# SD_A2.net
KiCad netlist of a schematic drawn in EAGLE
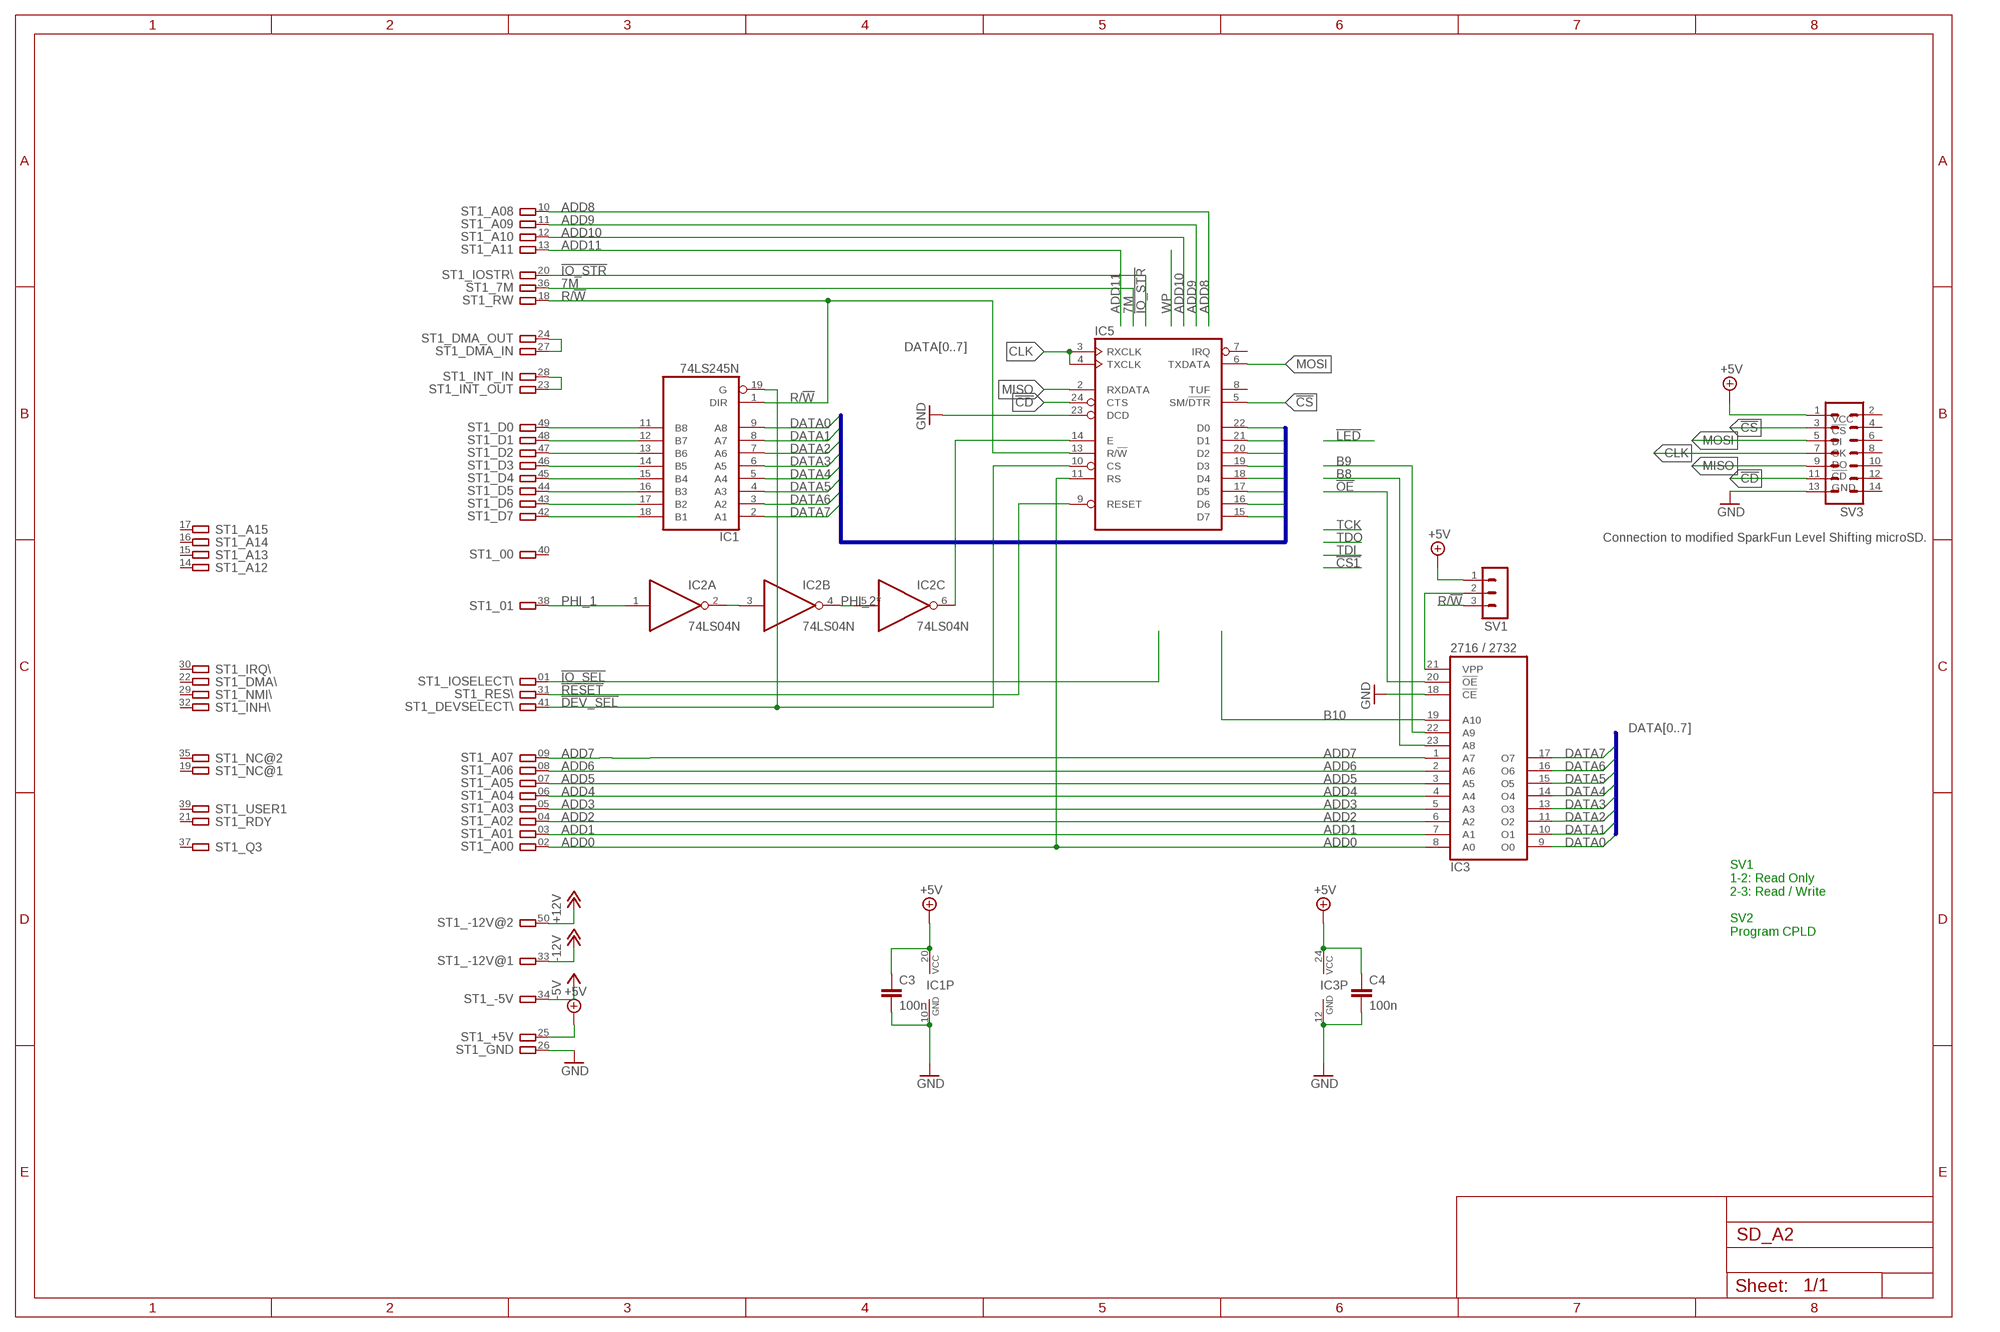
[diagram p0: schematic, sheet 1]

(export (version "E")
  (design (tool "Eeschema 10.0.6"))
  (components
    (comp (ref "C3")
      (value "100n")
      (footprint "eagle-import:C0603K")
      (libsource (lib "eagle-import") (part "C-EUC0603K"))
    )
    (comp (ref "C4")
      (value "100n")
      (footprint "eagle-import:C0603K")
      (libsource (lib "eagle-import") (part "C-EUC0603K"))
    )
    (comp (ref "IC1")
      (value "74LS245N")
      (footprint "eagle-import:DIL20")
      (libsource (lib "eagle-import") (part "74245NLS"))
    )
    (comp (ref "IC2")
      (value "74LS04N")
      (footprint "eagle-import:DIL14")
      (libsource (lib "eagle-import") (part "7404NLS"))
    )
    (comp (ref "IC3")
      (value "2716 / 2732")
      (footprint "eagle-import:DIL24")
      (libsource (lib "eagle-import") (part "2716"))
    )
    (comp (ref "IC5")
      (value "6852")
      (footprint "eagle-import:DIL24")
      (libsource (lib "eagle-import") (part "6852"))
    )
    (comp (ref "ST1")
      (value "A2-50PINSLOT1-3")
      (footprint "eagle-import:A2-50PIN-SL1-3")
      (libsource (lib "eagle-import") (part "A2-50PINSLOT1-3"))
    )
    (comp (ref "SV1")
      (value "MA03-1")
      (footprint "eagle-import:MA03-1")
      (libsource (lib "eagle-import") (part "MA03-1"))
    )
    (comp (ref "SV3")
      (value "MA07-2")
      (footprint "eagle-import:MA07-2")
      (libsource (lib "eagle-import") (part "MA07-2"))
    )
  )
  (nets
    (net (code "1") (name "+5V") (class "Default")
      (node (ref "C3") (pin "1") (pinfunction "1_1") (pintype "passive"))
      (node (ref "C4") (pin "1") (pinfunction "1_1") (pintype "passive"))
      (node (ref "IC1") (pin "20") (pinfunction "VCC_20") (pintype "power_in"))
      (node (ref "IC3") (pin "24") (pinfunction "VCC_24") (pintype "power_in"))
      (node (ref "ST1") (pin "25") (pinfunction "P_25") (pintype "bidirectional"))
      (node (ref "SV1") (pin "1") (pinfunction "1_1") (pintype "passive"))
      (node (ref "SV3") (pin "1") (pinfunction "1_1") (pintype "passive"))
    )
    (net (code "2") (name "+12V") (class "Default")
      (node (ref "ST1") (pin "50") (pinfunction "P_50") (pintype "bidirectional"))
    )
    (net (code "3") (name "-5V") (class "Default")
      (node (ref "ST1") (pin "34") (pinfunction "P_34") (pintype "bidirectional"))
    )
    (net (code "4") (name "-12V") (class "Default")
      (node (ref "ST1") (pin "33") (pinfunction "P_33") (pintype "bidirectional"))
    )
    (net (code "5") (name "/7M") (class "Default")
      (node (ref "ST1") (pin "36") (pinfunction "P_36") (pintype "bidirectional"))
    )
    (net (code "6") (name "/ADD0") (class "Default")
      (node (ref "IC3") (pin "8") (pinfunction "A0_8") (pintype "input"))
      (node (ref "IC5") (pin "11") (pinfunction "RS_11") (pintype "input"))
      (node (ref "ST1") (pin "02") (pinfunction "P_02") (pintype "bidirectional"))
    )
    (net (code "7") (name "/ADD1") (class "Default")
      (node (ref "IC3") (pin "7") (pinfunction "A1_7") (pintype "input"))
      (node (ref "ST1") (pin "03") (pinfunction "P_03") (pintype "bidirectional"))
    )
    (net (code "8") (name "/ADD2") (class "Default")
      (node (ref "IC3") (pin "6") (pinfunction "A2_6") (pintype "input"))
      (node (ref "ST1") (pin "04") (pinfunction "P_04") (pintype "bidirectional"))
    )
    (net (code "9") (name "/ADD3") (class "Default")
      (node (ref "IC3") (pin "5") (pinfunction "A3_5") (pintype "input"))
      (node (ref "ST1") (pin "05") (pinfunction "P_05") (pintype "bidirectional"))
    )
    (net (code "10") (name "/ADD4") (class "Default")
      (node (ref "IC3") (pin "4") (pinfunction "A4_4") (pintype "input"))
      (node (ref "ST1") (pin "06") (pinfunction "P_06") (pintype "bidirectional"))
    )
    (net (code "11") (name "/ADD5") (class "Default")
      (node (ref "IC3") (pin "3") (pinfunction "A5_3") (pintype "input"))
      (node (ref "ST1") (pin "07") (pinfunction "P_07") (pintype "bidirectional"))
    )
    (net (code "12") (name "/ADD6") (class "Default")
      (node (ref "IC3") (pin "2") (pinfunction "A6_2") (pintype "input"))
      (node (ref "ST1") (pin "08") (pinfunction "P_08") (pintype "bidirectional"))
    )
    (net (code "13") (name "/ADD7") (class "Default")
      (node (ref "IC3") (pin "1") (pinfunction "A7_1") (pintype "input"))
      (node (ref "ST1") (pin "09") (pinfunction "P_09") (pintype "bidirectional"))
    )
    (net (code "14") (name "/ADD8") (class "Default")
      (node (ref "ST1") (pin "10") (pinfunction "P_10") (pintype "bidirectional"))
    )
    (net (code "15") (name "/ADD9") (class "Default")
      (node (ref "ST1") (pin "11") (pinfunction "P_11") (pintype "bidirectional"))
    )
    (net (code "16") (name "/ADD10") (class "Default")
      (node (ref "ST1") (pin "12") (pinfunction "P_12") (pintype "bidirectional"))
    )
    (net (code "17") (name "/ADD11") (class "Default")
      (node (ref "ST1") (pin "13") (pinfunction "P_13") (pintype "bidirectional"))
    )
    (net (code "18") (name "/B8") (class "Default")
      (node (ref "IC3") (pin "23") (pinfunction "A8_23") (pintype "input"))
    )
    (net (code "19") (name "/B9") (class "Default")
      (node (ref "IC3") (pin "22") (pinfunction "A9_22") (pintype "input"))
    )
    (net (code "20") (name "/B10") (class "Default")
      (node (ref "IC3") (pin "19") (pinfunction "A10_19") (pintype "input"))
    )
    (net (code "21") (name "/DATA0") (class "Default")
      (node (ref "IC1") (pin "9") (pinfunction "A8_9") (pintype "bidirectional"))
      (node (ref "IC3") (pin "9") (pinfunction "O0_9") (pintype "tri_state"))
      (node (ref "IC5") (pin "22") (pinfunction "D0_22") (pintype "bidirectional"))
    )
    (net (code "22") (name "/DATA1") (class "Default")
      (node (ref "IC1") (pin "8") (pinfunction "A7_8") (pintype "bidirectional"))
      (node (ref "IC3") (pin "10") (pinfunction "O1_10") (pintype "tri_state"))
      (node (ref "IC5") (pin "21") (pinfunction "D1_21") (pintype "bidirectional"))
    )
    (net (code "23") (name "/DATA2") (class "Default")
      (node (ref "IC1") (pin "7") (pinfunction "A6_7") (pintype "bidirectional"))
      (node (ref "IC3") (pin "11") (pinfunction "O2_11") (pintype "tri_state"))
      (node (ref "IC5") (pin "20") (pinfunction "D2_20") (pintype "bidirectional"))
    )
    (net (code "24") (name "/DATA3") (class "Default")
      (node (ref "IC1") (pin "6") (pinfunction "A5_6") (pintype "bidirectional"))
      (node (ref "IC3") (pin "13") (pinfunction "O3_13") (pintype "tri_state"))
      (node (ref "IC5") (pin "19") (pinfunction "D3_19") (pintype "bidirectional"))
    )
    (net (code "25") (name "/DATA4") (class "Default")
      (node (ref "IC1") (pin "5") (pinfunction "A4_5") (pintype "bidirectional"))
      (node (ref "IC3") (pin "14") (pinfunction "O4_14") (pintype "tri_state"))
      (node (ref "IC5") (pin "18") (pinfunction "D4_18") (pintype "bidirectional"))
    )
    (net (code "26") (name "/DATA5") (class "Default")
      (node (ref "IC1") (pin "4") (pinfunction "A3_4") (pintype "bidirectional"))
      (node (ref "IC3") (pin "15") (pinfunction "O5_15") (pintype "tri_state"))
      (node (ref "IC5") (pin "17") (pinfunction "D5_17") (pintype "bidirectional"))
    )
    (net (code "27") (name "/DATA6") (class "Default")
      (node (ref "IC1") (pin "3") (pinfunction "A2_3") (pintype "bidirectional"))
      (node (ref "IC3") (pin "16") (pinfunction "O6_16") (pintype "tri_state"))
      (node (ref "IC5") (pin "16") (pinfunction "D6_16") (pintype "bidirectional"))
    )
    (net (code "28") (name "/DATA7") (class "Default")
      (node (ref "IC1") (pin "2") (pinfunction "A1_2") (pintype "bidirectional"))
      (node (ref "IC3") (pin "17") (pinfunction "O7_17") (pintype "tri_state"))
      (node (ref "IC5") (pin "15") (pinfunction "D7_15") (pintype "bidirectional"))
    )
    (net (code "30") (name "/PHI_1") (class "Default")
      (node (ref "IC2") (pin "1") (pinfunction "I_1") (pintype "input"))
      (node (ref "ST1") (pin "38") (pinfunction "P_38") (pintype "bidirectional"))
    )
    (net (code "31") (name "/PHI_2*") (class "Default")
      (node (ref "IC2") (pin "6") (pinfunction "O_6") (pintype "output"))
      (node (ref "IC5") (pin "14") (pinfunction "E_14") (pintype "input"))
    )
    (net (code "32") (name "/R{slash}~{W}") (class "Default")
      (node (ref "IC1") (pin "1") (pinfunction "DIR_1") (pintype "input"))
      (node (ref "IC5") (pin "13") (pinfunction "R/~{W}_13") (pintype "input"))
      (node (ref "ST1") (pin "18") (pinfunction "P_18") (pintype "bidirectional"))
      (node (ref "SV1") (pin "3") (pinfunction "3_3") (pintype "passive"))
    )
    (net (code "37") (name "/~{CD}") (class "Default")
      (node (ref "IC5") (pin "24") (pinfunction "CTS_24") (pintype "input"))
      (node (ref "SV3") (pin "11") (pinfunction "11_11") (pintype "passive"))
    )
    (net (code "39") (name "/~{CS}") (class "Default")
      (node (ref "IC5") (pin "5") (pinfunction "SM/~{DTR}_5") (pintype "output"))
      (node (ref "SV3") (pin "3") (pinfunction "3_3") (pintype "passive"))
    )
    (net (code "40") (name "/~{DEV_SEL}") (class "Default")
      (node (ref "IC1") (pin "19") (pinfunction "G_19") (pintype "input"))
      (node (ref "IC5") (pin "10") (pinfunction "CS_10") (pintype "input"))
      (node (ref "ST1") (pin "41") (pinfunction "P_41") (pintype "bidirectional"))
    )
    (net (code "41") (name "/~{IO_SEL}") (class "Default")
      (node (ref "ST1") (pin "01") (pinfunction "P_01") (pintype "bidirectional"))
    )
    (net (code "42") (name "/~{IO_STR}") (class "Default")
      (node (ref "ST1") (pin "20") (pinfunction "P_20") (pintype "bidirectional"))
    )
    (net (code "44") (name "/~{OE}") (class "Default")
      (node (ref "IC3") (pin "20") (pinfunction "~{OE}_20") (pintype "input"))
    )
    (net (code "45") (name "/~{RESET}") (class "Default")
      (node (ref "IC5") (pin "9") (pinfunction "RESET_9") (pintype "input"))
      (node (ref "ST1") (pin "31") (pinfunction "P_31") (pintype "bidirectional"))
    )
    (net (code "46") (name "CLK") (class "Default")
      (node (ref "IC5") (pin "3") (pinfunction "RXCLK_3") (pintype "input"))
      (node (ref "IC5") (pin "4") (pinfunction "TXCLK_4") (pintype "input"))
      (node (ref "SV3") (pin "7") (pinfunction "7_7") (pintype "passive"))
    )
    (net (code "47") (name "GND") (class "Default")
      (node (ref "C3") (pin "2") (pinfunction "2_2") (pintype "passive"))
      (node (ref "C4") (pin "2") (pinfunction "2_2") (pintype "passive"))
      (node (ref "IC1") (pin "10") (pinfunction "GND_10") (pintype "power_in"))
      (node (ref "IC3") (pin "12") (pinfunction "GND_12") (pintype "power_in"))
      (node (ref "IC3") (pin "18") (pinfunction "~{CE}_18") (pintype "input"))
      (node (ref "IC5") (pin "23") (pinfunction "DCD_23") (pintype "input"))
      (node (ref "ST1") (pin "26") (pinfunction "P_26") (pintype "bidirectional"))
      (node (ref "SV3") (pin "13") (pinfunction "13_13") (pintype "passive"))
    )
    (net (code "48") (name "MISO") (class "Default")
      (node (ref "IC5") (pin "2") (pinfunction "RXDATA_2") (pintype "input"))
      (node (ref "SV3") (pin "9") (pinfunction "9_9") (pintype "passive"))
    )
    (net (code "49") (name "MOSI") (class "Default")
      (node (ref "IC5") (pin "6") (pinfunction "TXDATA_6") (pintype "output"))
      (node (ref "SV3") (pin "5") (pinfunction "5_5") (pintype "passive"))
    )
    (net (code "50") (name "Net-(IC1A-B1)") (class "Default")
      (node (ref "IC1") (pin "18") (pinfunction "B1_18") (pintype "bidirectional"))
      (node (ref "ST1") (pin "42") (pinfunction "P_42") (pintype "bidirectional"))
    )
    (net (code "51") (name "Net-(IC1A-B2)") (class "Default")
      (node (ref "IC1") (pin "17") (pinfunction "B2_17") (pintype "bidirectional"))
      (node (ref "ST1") (pin "43") (pinfunction "P_43") (pintype "bidirectional"))
    )
    (net (code "52") (name "Net-(IC1A-B3)") (class "Default")
      (node (ref "IC1") (pin "16") (pinfunction "B3_16") (pintype "bidirectional"))
      (node (ref "ST1") (pin "44") (pinfunction "P_44") (pintype "bidirectional"))
    )
    (net (code "53") (name "Net-(IC1A-B4)") (class "Default")
      (node (ref "IC1") (pin "15") (pinfunction "B4_15") (pintype "bidirectional"))
      (node (ref "ST1") (pin "45") (pinfunction "P_45") (pintype "bidirectional"))
    )
    (net (code "54") (name "Net-(IC1A-B5)") (class "Default")
      (node (ref "IC1") (pin "14") (pinfunction "B5_14") (pintype "bidirectional"))
      (node (ref "ST1") (pin "46") (pinfunction "P_46") (pintype "bidirectional"))
    )
    (net (code "55") (name "Net-(IC1A-B6)") (class "Default")
      (node (ref "IC1") (pin "13") (pinfunction "B6_13") (pintype "bidirectional"))
      (node (ref "ST1") (pin "47") (pinfunction "P_47") (pintype "bidirectional"))
    )
    (net (code "56") (name "Net-(IC1A-B7)") (class "Default")
      (node (ref "IC1") (pin "12") (pinfunction "B7_12") (pintype "bidirectional"))
      (node (ref "ST1") (pin "48") (pinfunction "P_48") (pintype "bidirectional"))
    )
    (net (code "57") (name "Net-(IC1A-B8)") (class "Default")
      (node (ref "IC1") (pin "11") (pinfunction "B8_11") (pintype "bidirectional"))
      (node (ref "ST1") (pin "49") (pinfunction "P_49") (pintype "bidirectional"))
    )
    (net (code "58") (name "Net-(IC2A-O)") (class "Default")
      (node (ref "IC2") (pin "2") (pinfunction "O_2") (pintype "output"))
      (node (ref "IC2") (pin "3") (pinfunction "I_3") (pintype "input"))
    )
    (net (code "59") (name "Net-(IC2B-O)") (class "Default")
      (node (ref "IC2") (pin "4") (pinfunction "O_4") (pintype "output"))
      (node (ref "IC2") (pin "5") (pinfunction "I_5") (pintype "input"))
    )
    (net (code "60") (name "Net-(IC3A-VPP)") (class "Default")
      (node (ref "IC3") (pin "21") (pinfunction "VPP_21") (pintype "input"))
      (node (ref "SV1") (pin "2") (pinfunction "2_2") (pintype "passive"))
    )
    (net (code "61") (name "Net-(ST1AH-P)") (class "Default")
      (node (ref "ST1") (pin "24") (pinfunction "P_24") (pintype "bidirectional"))
      (node (ref "ST1") (pin "27") (pinfunction "P_27") (pintype "bidirectional"))
    )
    (net (code "62") (name "Net-(ST1AL-P)") (class "Default")
      (node (ref "ST1") (pin "23") (pinfunction "P_23") (pintype "bidirectional"))
      (node (ref "ST1") (pin "28") (pinfunction "P_28") (pintype "bidirectional"))
    )
    (net (code "63") (name "unconnected-(IC5A-IRQ-Pad7)") (class "Default")
      (node (ref "IC5") (pin "7") (pinfunction "IRQ_7") (pintype "output"))
    )
    (net (code "64") (name "unconnected-(IC5A-TUF-Pad8)") (class "Default")
      (node (ref "IC5") (pin "8") (pinfunction "TUF_8") (pintype "output"))
    )
    (net (code "65") (name "unconnected-(ST1AG-P-Pad22)") (class "Default")
      (node (ref "ST1") (pin "22") (pinfunction "P_22") (pintype "bidirectional"))
    )
    (net (code "66") (name "unconnected-(ST1AK-P-Pad32)") (class "Default")
      (node (ref "ST1") (pin "32") (pinfunction "P_32") (pintype "bidirectional"))
    )
    (net (code "67") (name "unconnected-(ST1AP-P-Pad30)") (class "Default")
      (node (ref "ST1") (pin "30") (pinfunction "P_30") (pintype "bidirectional"))
    )
    (net (code "68") (name "unconnected-(ST1AQ-P-Pad19)") (class "Default")
      (node (ref "ST1") (pin "19") (pinfunction "P_19") (pintype "bidirectional"))
    )
    (net (code "69") (name "unconnected-(ST1AR-P-Pad35)") (class "Default")
      (node (ref "ST1") (pin "35") (pinfunction "P_35") (pintype "bidirectional"))
    )
    (net (code "70") (name "unconnected-(ST1AS-P-Pad29)") (class "Default")
      (node (ref "ST1") (pin "29") (pinfunction "P_29") (pintype "bidirectional"))
    )
    (net (code "71") (name "unconnected-(ST1AT-P-Pad37)") (class "Default")
      (node (ref "ST1") (pin "37") (pinfunction "P_37") (pintype "bidirectional"))
    )
    (net (code "72") (name "unconnected-(ST1AU-P-Pad21)") (class "Default")
      (node (ref "ST1") (pin "21") (pinfunction "P_21") (pintype "bidirectional"))
    )
    (net (code "73") (name "unconnected-(ST1AX-P-Pad39)") (class "Default")
      (node (ref "ST1") (pin "39") (pinfunction "P_39") (pintype "bidirectional"))
    )
    (net (code "74") (name "unconnected-(ST1E-P-Pad40)") (class "Default")
      (node (ref "ST1") (pin "40") (pinfunction "P_40") (pintype "bidirectional"))
    )
    (net (code "75") (name "unconnected-(ST1T-P-Pad14)") (class "Default")
      (node (ref "ST1") (pin "14") (pinfunction "P_14") (pintype "bidirectional"))
    )
    (net (code "76") (name "unconnected-(ST1U-P-Pad15)") (class "Default")
      (node (ref "ST1") (pin "15") (pinfunction "P_15") (pintype "bidirectional"))
    )
    (net (code "77") (name "unconnected-(ST1V-P-Pad16)") (class "Default")
      (node (ref "ST1") (pin "16") (pinfunction "P_16") (pintype "bidirectional"))
    )
    (net (code "78") (name "unconnected-(ST1W-P-Pad17)") (class "Default")
      (node (ref "ST1") (pin "17") (pinfunction "P_17") (pintype "bidirectional"))
    )
    (net (code "79") (name "unconnected-(SV3-Pad2)") (class "Default")
      (node (ref "SV3") (pin "2") (pinfunction "2_2") (pintype "passive"))
    )
    (net (code "80") (name "unconnected-(SV3-Pad4)") (class "Default")
      (node (ref "SV3") (pin "4") (pinfunction "4_4") (pintype "passive"))
    )
    (net (code "81") (name "unconnected-(SV3-Pad6)") (class "Default")
      (node (ref "SV3") (pin "6") (pinfunction "6_6") (pintype "passive"))
    )
    (net (code "82") (name "unconnected-(SV3-Pad8)") (class "Default")
      (node (ref "SV3") (pin "8") (pinfunction "8_8") (pintype "passive"))
    )
    (net (code "83") (name "unconnected-(SV3-Pad10)") (class "Default")
      (node (ref "SV3") (pin "10") (pinfunction "10_10") (pintype "passive"))
    )
    (net (code "84") (name "unconnected-(SV3-Pad12)") (class "Default")
      (node (ref "SV3") (pin "12") (pinfunction "12_12") (pintype "passive"))
    )
    (net (code "85") (name "unconnected-(SV3-Pad14)") (class "Default")
      (node (ref "SV3") (pin "14") (pinfunction "14_14") (pintype "passive"))
    )
  )
)
